# Power_management.net
KiCad netlist of a schematic drawn in Altium Designer
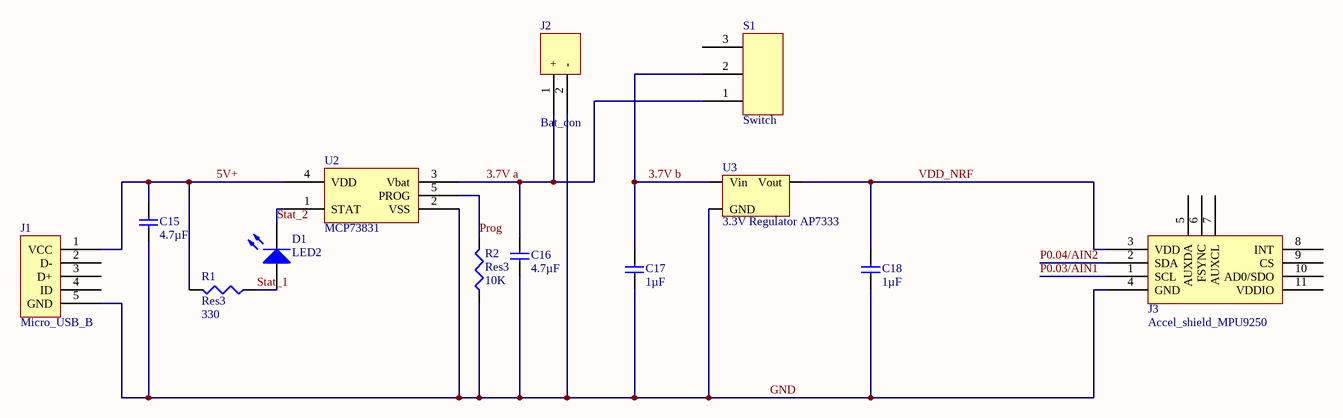
[diagram p0: Power_management.SchDoc]

(export (version "E")
  (design (tool "Eeschema 10.0.6"))
  (components
    (comp (ref "C15")
      (value "4.7µF")
      (footprint "CAPC1608X06L")
      (description "Capacitor, X5R, ±10%")
      (fields (field (name "PART NUMBER") "C0603-4µ7") (field (name "PUBLISHER") "Nordic Semiconductor"))
      (libsource (lib "nrf52832_qfax") (part "CAP_0603"))
    )
    (comp (ref "C16")
      (value "4.7µF")
      (footprint "CAPC1608X06L")
      (description "Capacitor, X5R, ±10%")
      (fields (field (name "PART NUMBER") "C0603-4µ7") (field (name "PUBLISHER") "Nordic Semiconductor"))
      (libsource (lib "nrf52832_qfax") (part "CAP_0603"))
    )
    (comp (ref "C17")
      (value "1µF")
      (footprint "CAPC1608X06L")
      (description "Capacitor, X5R, ±10%")
      (fields (field (name "PART NUMBER") "C0603-4µ7") (field (name "PUBLISHER") "Nordic Semiconductor"))
      (libsource (lib "nRF52832_Breakout_V2") (part "CAP_0603"))
    )
    (comp (ref "C18")
      (value "1µF")
      (footprint "CAPC1608X06L")
      (description "Capacitor, X5R, ±10%")
      (fields (field (name "PART NUMBER") "C0603-4µ7") (field (name "PUBLISHER") "Nordic Semiconductor"))
      (libsource (lib "nrf52832_qfax") (part "CAP_0603"))
    )
    (comp (ref "D1")
      (value "LED2")
      (footprint "LED_0603_G")
      (description "Typical RED, GREEN, YELLOW, AMBER GaAs LED")
      (fields (field (name "PUBLISHER") "Altium Limited"))
      (libsource (lib "Miscellaneous Devices") (part "LED2"))
    )
    (comp (ref "J1")
      (value "Micro_USB_B")
      (footprint "Micro_USB_AB")
      (libsource (lib "nRF52832_Breakout_V2") (part "Micro_USB_B"))
    )
    (comp (ref "J2")
      (value "Bat_con")
      (footprint "Bat_con")
      (libsource (lib "nRF52832_Breakout_V2") (part "Bat_con"))
    )
    (comp (ref "J3")
      (value "Accel_shield_MPU9250")
      (footprint "Accel_shield")
      (libsource (lib "nRF52832_Breakout_V2") (part "Accel_shield_MPU9250"))
    )
    (comp (ref "R1")
      (value "Res3")
      (footprint "J1-0603")
      (description "Resistor")
      (fields (field (name "ALTIUM_VALUE") "330") (field (name "PUBLISHER") "Altium Limited"))
      (libsource (lib "Miscellaneous Devices") (part "Res3"))
    )
    (comp (ref "R2")
      (value "Res3")
      (footprint "J1-0603")
      (description "Resistor")
      (fields (field (name "ALTIUM_VALUE") "10K") (field (name "PUBLISHER") "Altium Limited"))
      (libsource (lib "Miscellaneous Devices") (part "Res3"))
    )
    (comp (ref "S1")
      (value "Switch")
      (footprint "Switch")
      (libsource (lib "nRF52832_Breakout_V2") (part "Switch"))
    )
    (comp (ref "U2")
      (value "MCP73831")
      (footprint "SOT23-5")
      (libsource (lib "nrf52832_qfax") (part "MCP73831"))
    )
    (comp (ref "U3")
      (value "3.3V Regulator AP7333")
      (footprint "SOT-23A")
      (description "300mA, Low Quiescent Current, Fast Transient Low Dropout Linear Regulator")
      (fields
        (field (name "PART NUMBER") "AP7333-33SAG-7")
        (field (name "MANUFACTURER") "Diodes Incorporated")
        (field (name "PUBLISHER") "Nordic Semiconductor")
      )
      (libsource (lib "nrf52832_qfaa") (part "AP7333-XXSAG"))
    )
  )
  (nets
    (net (code "1") (name "/3.7V a") (class "Default")
      (node (ref "C16") (pin "2") (pinfunction "2_2") (pintype "passive"))
      (node (ref "J2") (pin "1") (pinfunction "+_1") (pintype "passive"))
      (node (ref "S1") (pin "1") (pintype "passive"))
      (node (ref "U2") (pin "3") (pinfunction "Vbat_3") (pintype "passive"))
    )
    (net (code "2") (name "/3.7V b") (class "Default")
      (node (ref "C17") (pin "2") (pinfunction "2_2") (pintype "passive"))
      (node (ref "S1") (pin "2") (pintype "passive"))
      (node (ref "U3") (pin "1") (pinfunction "Vin_1") (pintype "passive"))
    )
    (net (code "3") (name "/5V+") (class "Default")
      (node (ref "C15") (pin "2") (pinfunction "2_2") (pintype "passive"))
      (node (ref "J1") (pin "1") (pinfunction "VCC_1") (pintype "passive"))
      (node (ref "R1") (pin "2") (pinfunction "2_2") (pintype "passive"))
      (node (ref "U2") (pin "4") (pinfunction "VDD_4") (pintype "passive"))
    )
    (net (code "4") (name "/GND") (class "Default")
      (node (ref "C15") (pin "1") (pinfunction "1_1") (pintype "passive"))
      (node (ref "C16") (pin "1") (pinfunction "1_1") (pintype "passive"))
      (node (ref "C17") (pin "1") (pinfunction "1_1") (pintype "passive"))
      (node (ref "C18") (pin "1") (pinfunction "1_1") (pintype "passive"))
      (node (ref "J1") (pin "5") (pinfunction "GND_5") (pintype "passive"))
      (node (ref "J2") (pin "2") (pinfunction "-_2") (pintype "passive"))
      (node (ref "J3") (pin "4") (pinfunction "GND_4") (pintype "passive"))
      (node (ref "R2") (pin "1") (pinfunction "1_1") (pintype "passive"))
      (node (ref "U2") (pin "2") (pinfunction "VSS_2") (pintype "passive"))
      (node (ref "U3") (pin "3") (pinfunction "GND_3") (pintype "passive"))
    )
    (net (code "5") (name "/P0.03{slash}AIN1") (class "Default")
      (node (ref "J3") (pin "1") (pinfunction "SCL_1") (pintype "passive"))
    )
    (net (code "6") (name "/P0.04{slash}AIN2") (class "Default")
      (node (ref "J3") (pin "2") (pinfunction "SDA_2") (pintype "passive"))
    )
    (net (code "7") (name "/Prog") (class "Default")
      (node (ref "R2") (pin "2") (pinfunction "2_2") (pintype "passive"))
      (node (ref "U2") (pin "5") (pinfunction "PROG_5") (pintype "passive"))
    )
    (net (code "8") (name "/Stat_1") (class "Default")
      (node (ref "D1") (pin "1") (pinfunction "A_1") (pintype "passive"))
      (node (ref "R1") (pin "1") (pinfunction "1_1") (pintype "passive"))
    )
    (net (code "9") (name "/Stat_2") (class "Default")
      (node (ref "D1") (pin "2") (pinfunction "K_2") (pintype "passive"))
      (node (ref "U2") (pin "1") (pinfunction "STAT_1") (pintype "passive"))
    )
    (net (code "10") (name "/VDD_NRF") (class "Default")
      (node (ref "C18") (pin "2") (pinfunction "2_2") (pintype "passive"))
      (node (ref "J3") (pin "3") (pinfunction "VDD_3") (pintype "passive"))
      (node (ref "U3") (pin "2") (pinfunction "Vout_2") (pintype "passive"))
    )
    (net (code "11") (name "unconnected-(J1-D+-Pad3)") (class "Default")
      (node (ref "J1") (pin "3") (pinfunction "D+_3") (pintype "passive"))
    )
    (net (code "12") (name "unconnected-(J1-D--Pad2)") (class "Default")
      (node (ref "J1") (pin "2") (pinfunction "D-_2") (pintype "passive"))
    )
    (net (code "13") (name "unconnected-(J1-ID-Pad4)") (class "Default")
      (node (ref "J1") (pin "4") (pinfunction "ID_4") (pintype "passive"))
    )
    (net (code "14") (name "unconnected-(J3-AD0{slash}SDO-Pad10)") (class "Default")
      (node (ref "J3") (pin "10") (pinfunction "AD0/SDO_10") (pintype "passive"))
    )
    (net (code "15") (name "unconnected-(J3-AUXCL-Pad7)") (class "Default")
      (node (ref "J3") (pin "7") (pinfunction "AUXCL_7") (pintype "passive"))
    )
    (net (code "16") (name "unconnected-(J3-AUXDA-Pad5)") (class "Default")
      (node (ref "J3") (pin "5") (pinfunction "AUXDA_5") (pintype "passive"))
    )
    (net (code "17") (name "unconnected-(J3-CS-Pad9)") (class "Default")
      (node (ref "J3") (pin "9") (pinfunction "CS_9") (pintype "passive"))
    )
    (net (code "18") (name "unconnected-(J3-FSYNC-Pad6)") (class "Default")
      (node (ref "J3") (pin "6") (pinfunction "FSYNC_6") (pintype "passive"))
    )
    (net (code "19") (name "unconnected-(J3-INT-Pad8)") (class "Default")
      (node (ref "J3") (pin "8") (pinfunction "INT_8") (pintype "passive"))
    )
    (net (code "20") (name "unconnected-(J3-VDDIO-Pad11)") (class "Default")
      (node (ref "J3") (pin "11") (pinfunction "VDDIO_11") (pintype "passive"))
    )
    (net (code "21") (name "unconnected-(S1-Pad3)") (class "Default")
      (node (ref "S1") (pin "3") (pintype "passive"))
    )
  )
)
